# TDA2030_2_1.net
KiCad netlist of a schematic drawn in Altium Designer
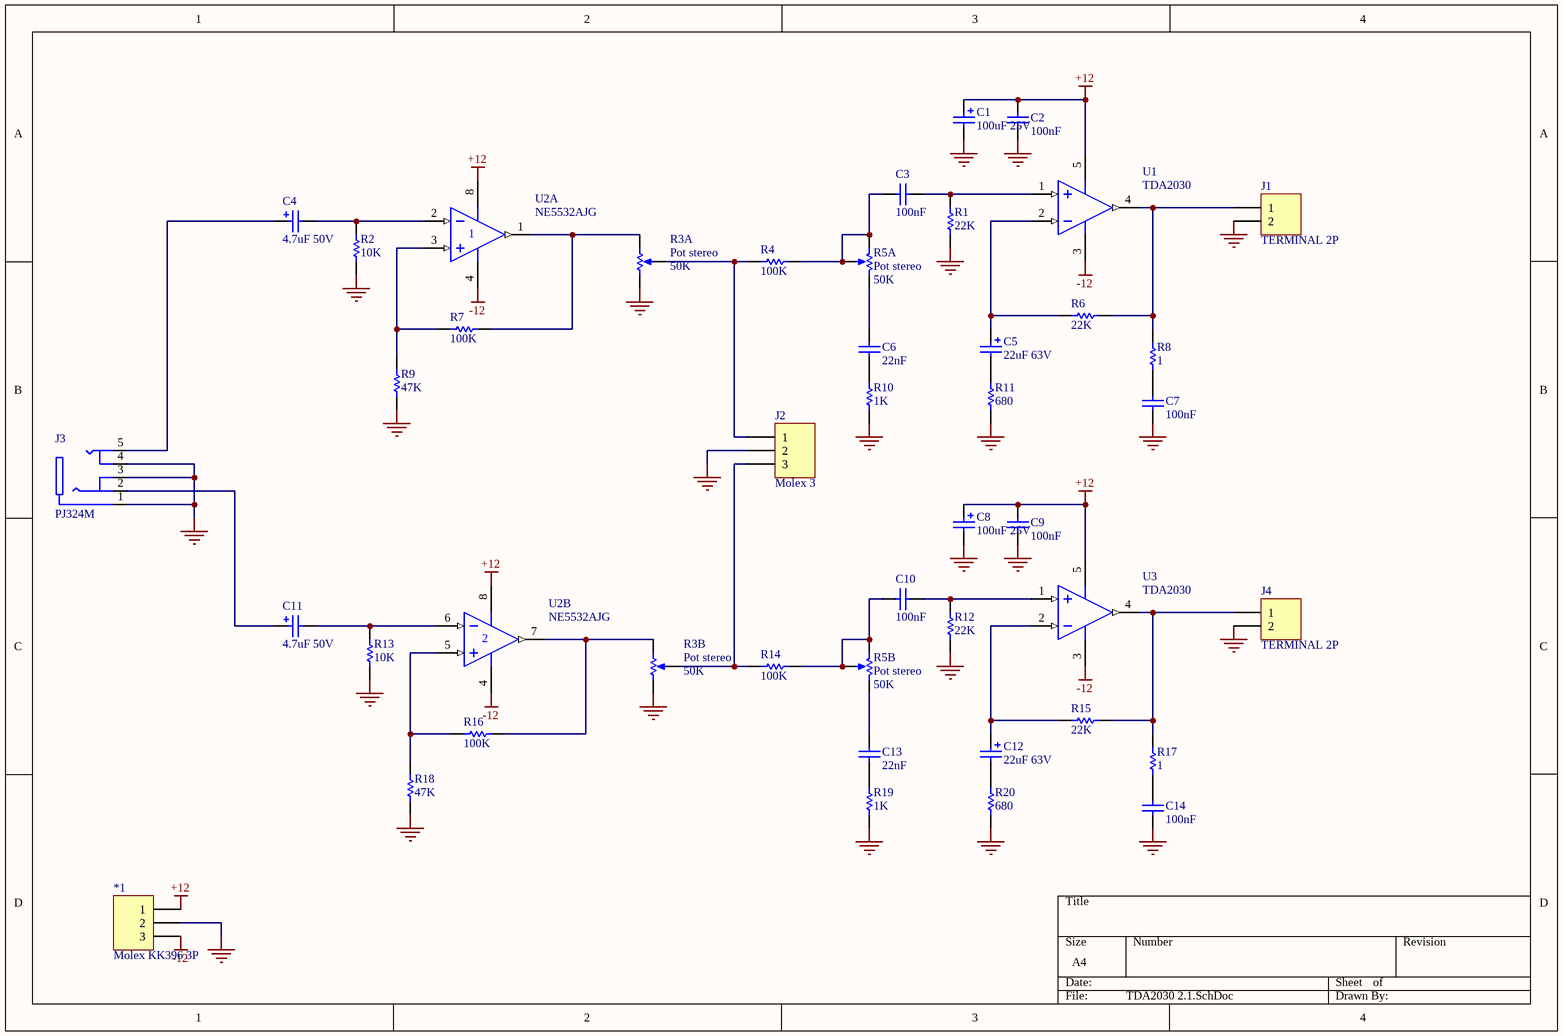
[diagram p0: TDA2030 2.1.SchDoc]

(export (version "E")
  (design (tool "Eeschema 10.0.6"))
  (components
    (comp (ref "*1")
      (value "Molex KK396 3P")
      (footprint "Molex kk396 3P")
      (libsource (lib "Schlib") (part "Molex KK396 3P"))
    )
    (comp (ref "C1")
      (value "100uF 25V")
      (footprint "100uF 25V")
      (description "Polarized Capacitor (Radial)")
      (fields (field (name "PUBLISHER") "Altium Limited"))
      (libsource (lib "Schlib") (part "100uF 25V"))
    )
    (comp (ref "C2")
      (value "100nF")
      (footprint "104")
      (description "Capacitor")
      (fields (field (name "PUBLISHER") "Altium Limited"))
      (libsource (lib "Schlib") (part "104"))
    )
    (comp (ref "C3")
      (value "100nF")
      (footprint "104")
      (description "Capacitor")
      (fields (field (name "PUBLISHER") "Altium Limited"))
      (libsource (lib "Schlib") (part "104"))
    )
    (comp (ref "C4")
      (value "4.7uF 50V")
      (footprint "4.7uF 50V")
      (description "Polarized Capacitor (Radial)")
      (fields (field (name "PUBLISHER") "Altium Limited"))
      (libsource (lib "Schlib") (part "4.7uF 50V"))
    )
    (comp (ref "C5")
      (value "22uF 63V")
      (footprint "22uF 63V")
      (description "Polarized Capacitor (Radial)")
      (fields (field (name "PUBLISHER") "Altium Limited"))
      (libsource (lib "Schlib") (part "22uF 63V"))
    )
    (comp (ref "C6")
      (value "22nF")
      (footprint "104")
      (description "Capacitor")
      (fields (field (name "PUBLISHER") "Altium Limited"))
      (libsource (lib "Schlib") (part "223"))
    )
    (comp (ref "C7")
      (value "100nF")
      (footprint "104")
      (description "Capacitor")
      (fields (field (name "PUBLISHER") "Altium Limited"))
      (libsource (lib "Schlib") (part "104"))
    )
    (comp (ref "C8")
      (value "100uF 25V")
      (footprint "100uF 25V")
      (description "Polarized Capacitor (Radial)")
      (fields (field (name "PUBLISHER") "Altium Limited"))
      (libsource (lib "Schlib") (part "100uF 25V"))
    )
    (comp (ref "C9")
      (value "100nF")
      (footprint "104")
      (description "Capacitor")
      (fields (field (name "PUBLISHER") "Altium Limited"))
      (libsource (lib "Schlib") (part "104"))
    )
    (comp (ref "C10")
      (value "100nF")
      (footprint "104")
      (description "Capacitor")
      (fields (field (name "PUBLISHER") "Altium Limited"))
      (libsource (lib "Schlib") (part "104"))
    )
    (comp (ref "C11")
      (value "4.7uF 50V")
      (footprint "4.7uF 50V")
      (description "Polarized Capacitor (Radial)")
      (fields (field (name "PUBLISHER") "Altium Limited"))
      (libsource (lib "Schlib") (part "4.7uF 50V"))
    )
    (comp (ref "C12")
      (value "22uF 63V")
      (footprint "22uF 63V")
      (description "Polarized Capacitor (Radial)")
      (fields (field (name "PUBLISHER") "Altium Limited"))
      (libsource (lib "Schlib") (part "22uF 63V"))
    )
    (comp (ref "C13")
      (value "22nF")
      (footprint "104")
      (description "Capacitor")
      (fields (field (name "PUBLISHER") "Altium Limited"))
      (libsource (lib "Schlib") (part "223"))
    )
    (comp (ref "C14")
      (value "100nF")
      (footprint "104")
      (description "Capacitor")
      (fields (field (name "PUBLISHER") "Altium Limited"))
      (libsource (lib "Schlib") (part "104"))
    )
    (comp (ref "J1")
      (value "TERMINAL 2P")
      (footprint "TERMINAL 2P")
      (description "Header, 2-Pin")
      (fields (field (name "PUBLISHER") "Altium Limited"))
      (libsource (lib "Schlib") (part "TERMINAL 2P"))
    )
    (comp (ref "J2")
      (value "Molex 3")
      (footprint "Molex kk100 3P")
      (description "Header, 3-Pin")
      (fields (field (name "PUBLISHER") "Altium Limited"))
      (libsource (lib "Schlib") (part "Molex kk100 3P"))
    )
    (comp (ref "J3")
      (value "PJ324M")
      (footprint "WENZHOU_PJ324M")
      (description "Headphone Stereo jack/Audio connector")
      (fields (field (name "MF") "Wenzhou QingPu Electronics Co.Ltd"))
      (libsource (lib "Schlib") (part "PJ324M"))
    )
    (comp (ref "J4")
      (value "TERMINAL 2P")
      (footprint "TERMINAL 2P")
      (description "Header, 2-Pin")
      (fields (field (name "PUBLISHER") "Altium Limited"))
      (libsource (lib "Schlib") (part "TERMINAL 2P"))
    )
    (comp (ref "R1")
      (value "22K")
      (footprint "AXIAL-0.4")
      (description "Resistor")
      (fields (field (name "PUBLISHER") "Altium Limited"))
      (libsource (lib "Miscellaneous Devices") (part "Res1"))
    )
    (comp (ref "R2")
      (value "10K")
      (footprint "AXIAL-0.4")
      (description "Resistor")
      (fields (field (name "PUBLISHER") "Altium Limited"))
      (libsource (lib "Miscellaneous Devices") (part "Res1"))
    )
    (comp (ref "R3")
      (value "Pot stereo")
      (footprint "Pote doble")
      (description "Potentiometer")
      (fields (field (name "ALTIUM_VALUE") "50K") (field (name "PUBLISHER") "Altium Limited"))
      (libsource (lib "Schlib") (part "RPot"))
    )
    (comp (ref "R4")
      (value "100K")
      (footprint "AXIAL-0.4")
      (description "Resistor")
      (fields (field (name "PUBLISHER") "Altium Limited"))
      (libsource (lib "Miscellaneous Devices") (part "Res1"))
    )
    (comp (ref "R5")
      (value "Pot stereo")
      (footprint "Pote doble")
      (description "Potentiometer")
      (fields (field (name "ALTIUM_VALUE") "50K") (field (name "PUBLISHER") "Altium Limited"))
      (libsource (lib "Schlib") (part "RPot"))
    )
    (comp (ref "R6")
      (value "22K")
      (footprint "AXIAL-0.4")
      (description "Resistor")
      (fields (field (name "PUBLISHER") "Altium Limited"))
      (libsource (lib "Miscellaneous Devices") (part "Res1"))
    )
    (comp (ref "R7")
      (value "100K")
      (footprint "AXIAL-0.4")
      (description "Resistor")
      (fields (field (name "PUBLISHER") "Altium Limited"))
      (libsource (lib "Miscellaneous Devices") (part "Res1"))
    )
    (comp (ref "R8")
      (value "1")
      (footprint "AXIAL-0.4")
      (description "Resistor")
      (fields (field (name "PUBLISHER") "Altium Limited"))
      (libsource (lib "Miscellaneous Devices") (part "Res1"))
    )
    (comp (ref "R9")
      (value "47K")
      (footprint "AXIAL-0.4")
      (description "Resistor")
      (fields (field (name "PUBLISHER") "Altium Limited"))
      (libsource (lib "Miscellaneous Devices") (part "Res1"))
    )
    (comp (ref "R10")
      (value "1K")
      (footprint "AXIAL-0.4")
      (description "Resistor")
      (fields (field (name "PUBLISHER") "Altium Limited"))
      (libsource (lib "Miscellaneous Devices") (part "Res1"))
    )
    (comp (ref "R11")
      (value "680")
      (footprint "AXIAL-0.4")
      (description "Resistor")
      (fields (field (name "PUBLISHER") "Altium Limited"))
      (libsource (lib "Miscellaneous Devices") (part "Res1"))
    )
    (comp (ref "R12")
      (value "22K")
      (footprint "AXIAL-0.4")
      (description "Resistor")
      (fields (field (name "PUBLISHER") "Altium Limited"))
      (libsource (lib "Miscellaneous Devices") (part "Res1"))
    )
    (comp (ref "R13")
      (value "10K")
      (footprint "AXIAL-0.4")
      (description "Resistor")
      (fields (field (name "PUBLISHER") "Altium Limited"))
      (libsource (lib "Miscellaneous Devices") (part "Res1"))
    )
    (comp (ref "R14")
      (value "100K")
      (footprint "AXIAL-0.4")
      (description "Resistor")
      (fields (field (name "PUBLISHER") "Altium Limited"))
      (libsource (lib "Miscellaneous Devices") (part "Res1"))
    )
    (comp (ref "R15")
      (value "22K")
      (footprint "AXIAL-0.4")
      (description "Resistor")
      (fields (field (name "PUBLISHER") "Altium Limited"))
      (libsource (lib "Miscellaneous Devices") (part "Res1"))
    )
    (comp (ref "R16")
      (value "100K")
      (footprint "AXIAL-0.4")
      (description "Resistor")
      (fields (field (name "PUBLISHER") "Altium Limited"))
      (libsource (lib "Miscellaneous Devices") (part "Res1"))
    )
    (comp (ref "R17")
      (value "1")
      (footprint "AXIAL-0.4")
      (description "Resistor")
      (fields (field (name "PUBLISHER") "Altium Limited"))
      (libsource (lib "Miscellaneous Devices") (part "Res1"))
    )
    (comp (ref "R18")
      (value "47K")
      (footprint "AXIAL-0.4")
      (description "Resistor")
      (fields (field (name "PUBLISHER") "Altium Limited"))
      (libsource (lib "Miscellaneous Devices") (part "Res1"))
    )
    (comp (ref "R19")
      (value "1K")
      (footprint "AXIAL-0.4 MIA")
      (description "Resistor")
      (fields (field (name "PUBLISHER") "Altium Limited"))
      (libsource (lib "Miscellaneous Devices") (part "Res1"))
    )
    (comp (ref "R20")
      (value "680")
      (footprint "AXIAL-0.4")
      (description "Resistor")
      (fields (field (name "PUBLISHER") "Altium Limited"))
      (libsource (lib "Miscellaneous Devices") (part "Res1"))
    )
    (comp (ref "U1") (value "TDA2030") (footprint "TDA2030") (libsource (lib "Schlib") (part "TDA2030")))
    (comp (ref "U2")
      (value "NE5532AJG")
      (footprint "JG008")
      (description "Dual Low-Noise Operational Amplifier")
      (fields (field (name "PUBLISHER") "Altium Limited"))
      (libsource (lib "TI Operational Amplifier") (part "NE5532AJG"))
    )
    (comp (ref "U3") (value "TDA2030") (footprint "TDA2030") (libsource (lib "Schlib") (part "TDA2030")))
  )
  (nets
    (net (code "1") (name "+12") (class "Default")
      (node (ref "*1") (pin "1") (pinfunction "1_1") (pintype "passive"))
      (node (ref "C1") (pin "1") (pinfunction "1_1") (pintype "passive"))
      (node (ref "C2") (pin "2") (pinfunction "2_2") (pintype "passive"))
      (node (ref "C8") (pin "1") (pinfunction "1_1") (pintype "passive"))
      (node (ref "C9") (pin "1") (pinfunction "1_1") (pintype "passive"))
      (node (ref "U1") (pin "5") (pinfunction "V+_5") (pintype "power_in"))
      (node (ref "U2") (pin "8") (pinfunction "V+_8") (pintype "power_in"))
      (node (ref "U3") (pin "5") (pinfunction "V+_5") (pintype "power_in"))
    )
    (net (code "2") (name "-12") (class "Default")
      (node (ref "*1") (pin "3") (pinfunction "3_3") (pintype "passive"))
      (node (ref "U1") (pin "3") (pinfunction "V-_3") (pintype "power_in"))
      (node (ref "U2") (pin "4") (pinfunction "V-_4") (pintype "power_in"))
      (node (ref "U3") (pin "3") (pinfunction "V-_3") (pintype "power_in"))
    )
    (net (code "3") (name "GND") (class "Default")
      (node (ref "*1") (pin "2") (pinfunction "2_2") (pintype "passive"))
      (node (ref "C1") (pin "2") (pinfunction "2_2") (pintype "passive"))
      (node (ref "C14") (pin "2") (pinfunction "2_2") (pintype "passive"))
      (node (ref "C2") (pin "1") (pinfunction "1_1") (pintype "passive"))
      (node (ref "C7") (pin "2") (pinfunction "2_2") (pintype "passive"))
      (node (ref "C8") (pin "2") (pinfunction "2_2") (pintype "passive"))
      (node (ref "C9") (pin "2") (pinfunction "2_2") (pintype "passive"))
      (node (ref "J1") (pin "2") (pinfunction "2_2") (pintype "passive"))
      (node (ref "J2") (pin "2") (pinfunction "2_2") (pintype "passive"))
      (node (ref "J3") (pin "1") (pinfunction "SLEEVE_1") (pintype "passive"))
      (node (ref "J3") (pin "3") (pinfunction "RING_2_3") (pintype "passive"))
      (node (ref "J3") (pin "4") (pinfunction "TIP_1_4") (pintype "passive"))
      (node (ref "J4") (pin "2") (pinfunction "2_2") (pintype "passive"))
      (node (ref "R1") (pin "1") (pinfunction "1_1") (pintype "passive"))
      (node (ref "R10") (pin "2") (pinfunction "2_2") (pintype "passive"))
      (node (ref "R11") (pin "1") (pinfunction "1_1") (pintype "passive"))
      (node (ref "R12") (pin "1") (pinfunction "1_1") (pintype "passive"))
      (node (ref "R13") (pin "2") (pinfunction "2_2") (pintype "passive"))
      (node (ref "R18") (pin "2") (pinfunction "2_2") (pintype "passive"))
      (node (ref "R19") (pin "2") (pinfunction "2_2") (pintype "passive"))
      (node (ref "R2") (pin "2") (pinfunction "2_2") (pintype "passive"))
      (node (ref "R20") (pin "1") (pinfunction "1_1") (pintype "passive"))
      (node (ref "R3") (pin "1") (pinfunction "TOP_1") (pintype "passive"))
      (node (ref "R3") (pin "4") (pinfunction "TOP_4") (pintype "passive"))
      (node (ref "R9") (pin "2") (pinfunction "2_2") (pintype "passive"))
    )
    (net (code "4") (name "Net-(C5-Pad2)") (class "Default")
      (node (ref "C5") (pin "2") (pinfunction "2_2") (pintype "passive"))
      (node (ref "R11") (pin "2") (pinfunction "2_2") (pintype "passive"))
    )
    (net (code "5") (name "Net-(C6-Pad1)") (class "Default")
      (node (ref "C6") (pin "1") (pinfunction "1_1") (pintype "passive"))
      (node (ref "R10") (pin "1") (pinfunction "1_1") (pintype "passive"))
    )
    (net (code "6") (name "Net-(C7-Pad1)") (class "Default")
      (node (ref "C7") (pin "1") (pinfunction "1_1") (pintype "passive"))
      (node (ref "R8") (pin "2") (pinfunction "2_2") (pintype "passive"))
    )
    (net (code "7") (name "Net-(C12-Pad2)") (class "Default")
      (node (ref "C12") (pin "2") (pinfunction "2_2") (pintype "passive"))
      (node (ref "R20") (pin "2") (pinfunction "2_2") (pintype "passive"))
    )
    (net (code "8") (name "Net-(C13-Pad1)") (class "Default")
      (node (ref "C13") (pin "1") (pinfunction "1_1") (pintype "passive"))
      (node (ref "R19") (pin "1") (pinfunction "1_1") (pintype "passive"))
    )
    (net (code "9") (name "Net-(C14-Pad1)") (class "Default")
      (node (ref "C14") (pin "1") (pinfunction "1_1") (pintype "passive"))
      (node (ref "R17") (pin "2") (pinfunction "2_2") (pintype "passive"))
    )
    (net (code "10") (name "Net-(J3-RING_1)") (class "Default")
      (node (ref "C11") (pin "1") (pinfunction "1_1") (pintype "passive"))
      (node (ref "J3") (pin "2") (pinfunction "RING_1_2") (pintype "passive"))
    )
    (net (code "11") (name "Net-(J3-TIP_2)") (class "Default")
      (node (ref "C4") (pin "1") (pinfunction "1_1") (pintype "passive"))
      (node (ref "J3") (pin "5") (pinfunction "TIP_2_5") (pintype "passive"))
    )
    (net (code "12") (name "Net-(R3A-BOT)") (class "Default")
      (node (ref "R3") (pin "3") (pinfunction "BOT_3") (pintype "passive"))
      (node (ref "R7") (pin "1") (pinfunction "1_1") (pintype "passive"))
      (node (ref "U2") (pin "1") (pinfunction "OUT_1") (pintype "output"))
    )
    (net (code "13") (name "Net-(R3A-TAP)") (class "Default")
      (node (ref "J2") (pin "1") (pinfunction "1_1") (pintype "passive"))
      (node (ref "R3") (pin "2") (pinfunction "TAP_2") (pintype "passive"))
      (node (ref "R4") (pin "2") (pinfunction "2_2") (pintype "passive"))
    )
    (net (code "14") (name "Net-(R3B-BOT)") (class "Default")
      (node (ref "R16") (pin "1") (pinfunction "1_1") (pintype "passive"))
      (node (ref "R3") (pin "6") (pinfunction "BOT_6") (pintype "passive"))
      (node (ref "U2") (pin "7") (pinfunction "OUT_7") (pintype "output"))
    )
    (net (code "15") (name "Net-(R3B-TAP)") (class "Default")
      (node (ref "J2") (pin "3") (pinfunction "3_3") (pintype "passive"))
      (node (ref "R14") (pin "2") (pinfunction "2_2") (pintype "passive"))
      (node (ref "R3") (pin "5") (pinfunction "TAP_5") (pintype "passive"))
    )
    (net (code "16") (name "Net-(R5A-BOT)") (class "Default")
      (node (ref "C3") (pin "2") (pinfunction "2_2") (pintype "passive"))
      (node (ref "R4") (pin "1") (pinfunction "1_1") (pintype "passive"))
      (node (ref "R5") (pin "2") (pinfunction "TAP_2") (pintype "passive"))
      (node (ref "R5") (pin "3") (pinfunction "BOT_3") (pintype "passive"))
    )
    (net (code "17") (name "Net-(R5A-TOP)") (class "Default")
      (node (ref "C6") (pin "2") (pinfunction "2_2") (pintype "passive"))
      (node (ref "R5") (pin "1") (pinfunction "TOP_1") (pintype "passive"))
    )
    (net (code "18") (name "Net-(R5B-BOT)") (class "Default")
      (node (ref "C10") (pin "2") (pinfunction "2_2") (pintype "passive"))
      (node (ref "R14") (pin "1") (pinfunction "1_1") (pintype "passive"))
      (node (ref "R5") (pin "5") (pinfunction "TAP_5") (pintype "passive"))
      (node (ref "R5") (pin "6") (pinfunction "BOT_6") (pintype "passive"))
    )
    (net (code "19") (name "Net-(R5B-TOP)") (class "Default")
      (node (ref "C13") (pin "2") (pinfunction "2_2") (pintype "passive"))
      (node (ref "R5") (pin "4") (pinfunction "TOP_4") (pintype "passive"))
    )
    (net (code "20") (name "Net-(U1-IN+)") (class "Default")
      (node (ref "C3") (pin "1") (pinfunction "1_1") (pintype "passive"))
      (node (ref "R1") (pin "2") (pinfunction "2_2") (pintype "passive"))
      (node (ref "U1") (pin "1") (pinfunction "IN+_1") (pintype "input"))
    )
    (net (code "21") (name "Net-(U1-IN-)") (class "Default")
      (node (ref "C5") (pin "1") (pinfunction "1_1") (pintype "passive"))
      (node (ref "R6") (pin "2") (pinfunction "2_2") (pintype "passive"))
      (node (ref "U1") (pin "2") (pinfunction "IN-_2") (pintype "input"))
    )
    (net (code "22") (name "Net-(U1-OUT)") (class "Default")
      (node (ref "J1") (pin "1") (pinfunction "1_1") (pintype "passive"))
      (node (ref "R6") (pin "1") (pinfunction "1_1") (pintype "passive"))
      (node (ref "R8") (pin "1") (pinfunction "1_1") (pintype "passive"))
      (node (ref "U1") (pin "4") (pinfunction "OUT_4") (pintype "output"))
    )
    (net (code "23") (name "Net-(U2A-IN+)") (class "Default")
      (node (ref "R7") (pin "2") (pinfunction "2_2") (pintype "passive"))
      (node (ref "R9") (pin "1") (pinfunction "1_1") (pintype "passive"))
      (node (ref "U2") (pin "3") (pinfunction "IN+_3") (pintype "input"))
    )
    (net (code "24") (name "Net-(U2A-IN-)") (class "Default")
      (node (ref "C4") (pin "2") (pinfunction "2_2") (pintype "passive"))
      (node (ref "R2") (pin "1") (pinfunction "1_1") (pintype "passive"))
      (node (ref "U2") (pin "2") (pinfunction "IN-_2") (pintype "input"))
    )
    (net (code "25") (name "Net-(U2B-IN+)") (class "Default")
      (node (ref "R16") (pin "2") (pinfunction "2_2") (pintype "passive"))
      (node (ref "R18") (pin "1") (pinfunction "1_1") (pintype "passive"))
      (node (ref "U2") (pin "5") (pinfunction "IN+_5") (pintype "input"))
    )
    (net (code "26") (name "Net-(U2B-IN-)") (class "Default")
      (node (ref "C11") (pin "2") (pinfunction "2_2") (pintype "passive"))
      (node (ref "R13") (pin "1") (pinfunction "1_1") (pintype "passive"))
      (node (ref "U2") (pin "6") (pinfunction "IN-_6") (pintype "input"))
    )
    (net (code "27") (name "Net-(U3-IN+)") (class "Default")
      (node (ref "C10") (pin "1") (pinfunction "1_1") (pintype "passive"))
      (node (ref "R12") (pin "2") (pinfunction "2_2") (pintype "passive"))
      (node (ref "U3") (pin "1") (pinfunction "IN+_1") (pintype "input"))
    )
    (net (code "28") (name "Net-(U3-IN-)") (class "Default")
      (node (ref "C12") (pin "1") (pinfunction "1_1") (pintype "passive"))
      (node (ref "R15") (pin "2") (pinfunction "2_2") (pintype "passive"))
      (node (ref "U3") (pin "2") (pinfunction "IN-_2") (pintype "input"))
    )
    (net (code "29") (name "Net-(U3-OUT)") (class "Default")
      (node (ref "J4") (pin "1") (pinfunction "1_1") (pintype "passive"))
      (node (ref "R15") (pin "1") (pinfunction "1_1") (pintype "passive"))
      (node (ref "R17") (pin "1") (pinfunction "1_1") (pintype "passive"))
      (node (ref "U3") (pin "4") (pinfunction "OUT_4") (pintype "output"))
    )
  )
)
